# Smart_OBD.net
KiCad netlist of a schematic drawn in Altium Designer
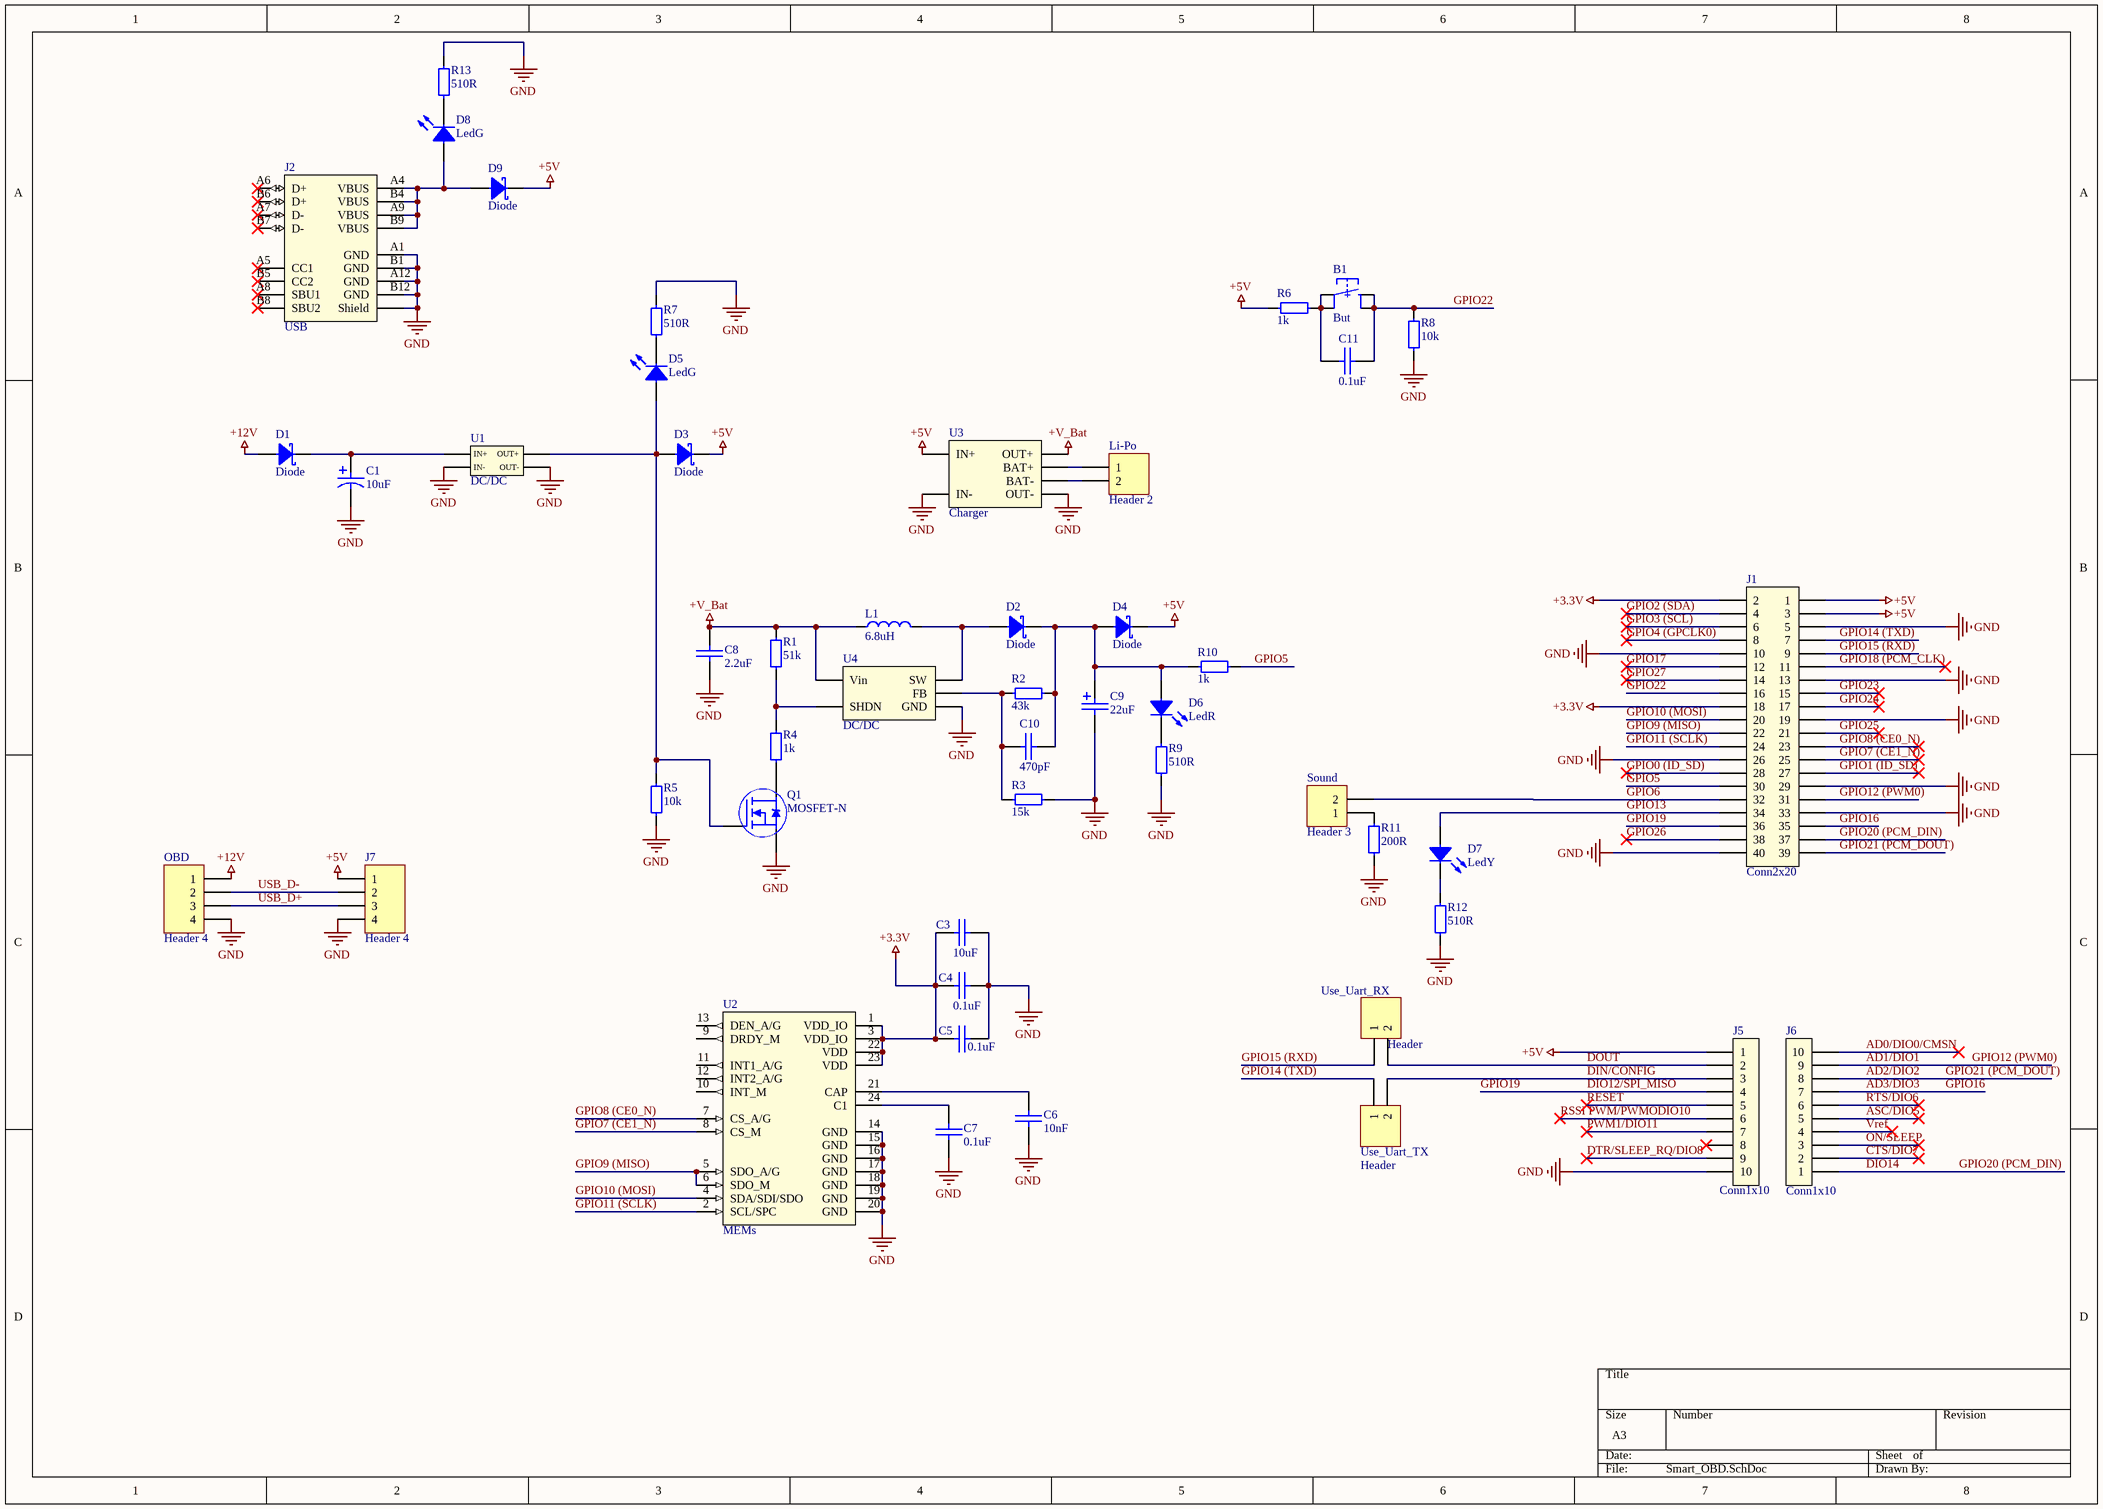
[diagram p0: Smart_OBD.SchDoc]

(export (version "E")
  (design (tool "Eeschema 10.0.6"))
  (components
    (comp (ref "B1")
      (value "But")
      (footprint "Button 6x6")
      (description "Button 4 Conn SMD")
      (fields (field (name "MANUFACTURER") "TE Connectivity") (field (name "PART NUMBER") "1571563-9"))
      (libsource (lib "Karen_Components") (part "Button 4 Conn"))
    )
    (comp (ref "C1")
      (value "10uF")
      (footprint "Bar Cap 5x5.4")
      (description "ECAP SMD,  35V")
      (fields (field (name "PART NUMBER") "ECAPSMD10uF/35V") (field (name "MANUFACTURER") "China"))
      (libsource (lib "Karen_Components") (part "Cap Pol 10uF"))
    )
    (comp (ref "C3")
      (value "10uF")
      (footprint "0603 Capicator")
      (description "10uF X5R 25V 20% 0603")
      (fields
        (field (name "MANUFACTURER") "Murata Manufacturing")
        (field (name "PART NUMBER") "GRM188R61E106M")
      )
      (libsource (lib "Karen_Components") (part "Cap 10uF (0603)"))
    )
    (comp (ref "C4")
      (value "0.1uF")
      (footprint "0603 Capicator")
      (description "0.1uF X7R 50V 10% 0603")
      (fields
        (field (name "MANUFACTURER") "Murata Manufacturing")
        (field (name "PART NUMBER") "GRM188R71H104KA93D")
      )
      (libsource (lib "Karen_Components") (part "Cap 0.1uF (0603)"))
    )
    (comp (ref "C5")
      (value "0.1uF")
      (footprint "0603 Capicator")
      (description "0.1uF X7R 50V 10% 0603")
      (fields
        (field (name "MANUFACTURER") "Murata Manufacturing")
        (field (name "PART NUMBER") "GRM188R71H104KA93D")
      )
      (libsource (lib "Karen_Components") (part "Cap 0.1uF (0603)"))
    )
    (comp (ref "C6")
      (value "10nF")
      (footprint "0603 Capicator")
      (description "X7R 10nF 100V 10% 0603")
      (fields
        (field (name "MANUFACTURER") "Murata Manufacturing")
        (field (name "PART NUMBER") "GRM188R72A103KA01D")
      )
      (libsource (lib "Karen_Components") (part "Cap 10nF (0603)"))
    )
    (comp (ref "C7")
      (value "0.1uF")
      (footprint "0603 Capicator")
      (description "0.1uF X7R 50V 10% 0603")
      (fields
        (field (name "MANUFACTURER") "Murata Manufacturing")
        (field (name "PART NUMBER") "GRM188R71H104KA93D")
      )
      (libsource (lib "Karen_Components") (part "Cap 0.1uF (0603)"))
    )
    (comp (ref "C8")
      (value "2.2uF")
      (footprint "0603 Capicator")
      (description "2.2uF X5R 10V 10% 0603")
      (fields
        (field (name "MANUFACTURER") "Murata Manufacturing")
        (field (name "PART NUMBER") "GRM188R61A225KE34D")
      )
      (libsource (lib "Karen_Components") (part "Cap 2.2uF (0603)"))
    )
    (comp (ref "C9")
      (value "22uF")
      (footprint "TANTAL_C_CASE")
      (description "TECAP, 22uF, 16V, case C, 10%")
      (fields (field (name "PART NUMBER") "TECAP22/16VC10") (field (name "MANUFACTURER") "China"))
      (libsource (lib "Karen_Components") (part "Cap Tantal 22uF (SMDC)"))
    )
    (comp (ref "C10")
      (value "470pF")
      (footprint "0603 Capicator")
      (description "470pF NP0 50V 5% 0603")
      (fields (field (name "MANUFACTURER") "Taiwan") (field (name "PART NUMBER") "MLCC470pFNPO50V5%0603"))
      (libsource (lib "Karen_Components") (part "Cap 470pF (0603)"))
    )
    (comp (ref "C11")
      (value "0.1uF")
      (footprint "0603 Capicator")
      (description "0.1uF X7R 50V 10% 0603")
      (fields
        (field (name "MANUFACTURER") "Murata Manufacturing")
        (field (name "PART NUMBER") "GRM188R71H104KA93D")
      )
      (libsource (lib "Karen_Components") (part "Cap 0.1uF (0603)"))
    )
    (comp (ref "D1")
      (value "Diode")
      (footprint "SMA")
      (description "Diode Schottky 3A 40V")
      (fields (field (name "PART NUMBER") "B340A-E3/61T") (field (name "MANUFACTURER") "Vishay"))
      (libsource (lib "Karen_Components") (part "Diode Schottky (SMA)"))
    )
    (comp (ref "D2")
      (value "Diode")
      (footprint "SMA")
      (description "Diode Schottky 3A 40V")
      (fields (field (name "PART NUMBER") "B340A-E3/61T") (field (name "MANUFACTURER") "Vishay"))
      (libsource (lib "Karen_Components") (part "Diode Schottky (SMA)"))
    )
    (comp (ref "D3")
      (value "Diode")
      (footprint "SMA")
      (description "Diode Schottky 3A 40V")
      (fields (field (name "PART NUMBER") "B340A-E3/61T") (field (name "MANUFACTURER") "Vishay"))
      (libsource (lib "Karen_Components") (part "Diode Schottky (SMA)"))
    )
    (comp (ref "D4")
      (value "Diode")
      (footprint "SMA")
      (description "Diode Schottky 3A 40V")
      (fields (field (name "PART NUMBER") "B340A-E3/61T") (field (name "MANUFACTURER") "Vishay"))
      (libsource (lib "Karen_Components") (part "Diode Schottky (SMA)"))
    )
    (comp (ref "D5")
      (value "LedG")
      (footprint "0805 LED")
      (description "Led Green SMD 1608, 120°, 525nM")
      (fields
        (field (name "PART NUMBER") "TO-1608BC-PG")
        (field (name "MANUFACTURER") "Taiwan Oasis Technology")
      )
      (libsource (lib "Karen_Components") (part "Led Green"))
    )
    (comp (ref "D6")
      (value "LedR")
      (footprint "0805 LED")
      (description "SMD 1608, 112mcd, 120°, 630nM (Ultra Bright Red)")
      (fields
        (field (name "PART NUMBER") "TO-1608BC-MRE")
        (field (name "MANUFACTURER") "Taiwan Oasis Technology")
      )
      (libsource (lib "Karen_Components") (part "Led Red"))
    )
    (comp (ref "D7")
      (value "LedY")
      (footprint "0805 LED")
      (description "SMD 1608, 247mcd, 120°, 592nM (High Bright Yellow)")
      (fields
        (field (name "PART NUMBER") "TO-1608BC-MYF")
        (field (name "MANUFACTURER") "Taiwan Oasis Technology")
      )
      (libsource (lib "Karen_Components") (part "Led Yellow"))
    )
    (comp (ref "D8")
      (value "LedG")
      (footprint "0805 LED")
      (description "Led Green SMD 1608, 120°, 525nM")
      (fields
        (field (name "PART NUMBER") "TO-1608BC-PG")
        (field (name "MANUFACTURER") "Taiwan Oasis Technology")
      )
      (libsource (lib "Karen_Components") (part "Led Green"))
    )
    (comp (ref "D9")
      (value "Diode")
      (footprint "SMA")
      (description "Diode Schottky 3A 40V")
      (fields (field (name "PART NUMBER") "B340A-E3/61T") (field (name "MANUFACTURER") "Vishay"))
      (libsource (lib "Karen_Components") (part "Diode Schottky (SMA)"))
    )
    (comp (ref "J1")
      (value "Conn2x20")
      (footprint "PBD 2x20")
      (description "Female for PLD")
      (fields
        (field (name "PART NUMBER") "DS1023-2*20S21")
        (field (name "MANUFACTURER") "Ningbo connfly electronic")
      )
      (libsource (lib "Karen_Components") (part "Conn2x20 (PBD)"))
    )
    (comp (ref "J2")
      (value "USB")
      (footprint "USB Type-C")
      (fields
        (field (name "MANUFACTURER") "Global Connector Technology")
        (field (name "PART NUMBER") "USB4085-GF-A")
      )
      (libsource (lib "Karen_Components") (part "Connector USB 2.0 Type-C"))
    )
    (comp (ref "J5")
      (value "Conn1x10")
      (footprint "PBS2 10")
      (description "Female")
      (fields
        (field (name "PART NUMBER") "DS1026-01-1*10S8BV")
        (field (name "MANUFACTURER") "Ningbo connfly electronic")
      )
      (libsource (lib "") (part "Conn1x10 (PBS2)_1"))
    )
    (comp (ref "J6")
      (value "Conn1x10")
      (footprint "PBS2 10")
      (description "Female")
      (fields
        (field (name "PART NUMBER") "DS1026-01-1*10S8BV")
        (field (name "MANUFACTURER") "Ningbo connfly electronic")
      )
      (libsource (lib "Karen_Components") (part "Conn1x10 (PBS2)"))
    )
    (comp (ref "J7")
      (value "Header 4")
      (footprint "HDR1X4")
      (description "Header, 4-Pin")
      (fields (field (name "PUBLISHER") "Altium Limited"))
      (libsource (lib "") (part "Header 4_1"))
    )
    (comp (ref "L1")
      (value "6.8uH")
      (footprint "Inductor 5.4x5.1")
      (description "6.8uH, 5.4x5.1x2, 4.2A")
      (fields (field (name "PART NUMBER") "SPM5020T-3R3M-LR") (field (name "MANUFACTURER") "TDK"))
      (libsource (lib "Karen_Components") (part "Inductor 6.8uH (4.2A)"))
    )
    (comp (ref "Li-Po")
      (value "Header 2")
      (footprint "HDR1X2")
      (description "Header, 2-Pin")
      (fields (field (name "PUBLISHER") "Altium Limited"))
      (libsource (lib "") (part "Header 2_1"))
    )
    (comp (ref "OBD")
      (value "Header 4")
      (footprint "HDR1X4")
      (description "Header, 4-Pin")
      (fields (field (name "PUBLISHER") "Altium Limited"))
      (libsource (lib "Miscellaneous Connectors") (part "Header 4"))
    )
    (comp (ref "Q1")
      (value "MOSFET-N")
      (footprint "SOT-23")
      (fields (field (name "PART NUMBER") "FDV303N") (field (name "MANUFACTURER") "Fairchild Semiconductor"))
      (libsource (lib "Karen_Components") (part "MOSFET-N [FDV]"))
    )
    (comp (ref "R1")
      (value "51k")
      (footprint "0603 Resistor")
      (description "0.1W 0603 51k, 1%")
      (fields (field (name "PART NUMBER") "RC0603FR-0751KL") (field (name "MANUFACTURER") "Taiwan"))
      (libsource (lib "Karen_Components") (part "Res 51k (0603)"))
    )
    (comp (ref "R2")
      (value "43k")
      (footprint "0603 Resistor")
      (description "0.1W 0603 43k, 1%")
      (fields (field (name "PART NUMBER") "RC0603FR-0743KL") (field (name "MANUFACTURER") "Taiwan"))
      (libsource (lib "Karen_Components") (part "Res 43k (0603)"))
    )
    (comp (ref "R3")
      (value "15k")
      (footprint "0603 Resistor")
      (description "0.1W 0603 15k, 1%")
      (fields (field (name "PART NUMBER") "RC0603FR-0715KL") (field (name "MANUFACTURER") "Taiwan"))
      (libsource (lib "Karen_Components") (part "Res 15k (0603)"))
    )
    (comp (ref "R4")
      (value "1k")
      (footprint "0603 Resistor")
      (description "0.1W 0603 1k, 1%")
      (fields (field (name "PART NUMBER") "RC0603FR-071KL") (field (name "MANUFACTURER") "Taiwan"))
      (libsource (lib "Karen_Components") (part "Res 1k (0603)"))
    )
    (comp (ref "R5")
      (value "10k")
      (footprint "0603 Resistor")
      (description "0.1W 0603 10k, 1%")
      (fields (field (name "PART NUMBER") "RC0603FR-0710KL") (field (name "MANUFACTURER") "Taiwan"))
      (libsource (lib "Karen_Components") (part "Res 10k (0603)"))
    )
    (comp (ref "R6")
      (value "1k")
      (footprint "0603 Resistor")
      (description "0.1W 0603 1k, 1%")
      (fields (field (name "PART NUMBER") "RC0603FR-071KL") (field (name "MANUFACTURER") "Taiwan"))
      (libsource (lib "Karen_Components") (part "Res 1k (0603)"))
    )
    (comp (ref "R7")
      (value "510R")
      (footprint "0603 Resistor")
      (description "0.1W 0603 510R, 1%")
      (fields (field (name "PART NUMBER") "RC0603FR-07510RL") (field (name "MANUFACTURER") "Taiwan"))
      (libsource (lib "Karen_Components") (part "Res 510R (0603)"))
    )
    (comp (ref "R8")
      (value "10k")
      (footprint "0603 Resistor")
      (description "0.1W 0603 10k, 1%")
      (fields (field (name "PART NUMBER") "RC0603FR-0710KL") (field (name "MANUFACTURER") "Taiwan"))
      (libsource (lib "Karen_Components") (part "Res 10k (0603)"))
    )
    (comp (ref "R9")
      (value "510R")
      (footprint "0603 Resistor")
      (description "0.1W 0603 510R, 1%")
      (fields (field (name "PART NUMBER") "RC0603FR-07510RL") (field (name "MANUFACTURER") "Taiwan"))
      (libsource (lib "Karen_Components") (part "Res 510R (0603)"))
    )
    (comp (ref "R10")
      (value "1k")
      (footprint "0603 Resistor")
      (description "0.1W 0603 1k, 1%")
      (fields (field (name "PART NUMBER") "RC0603FR-071KL") (field (name "MANUFACTURER") "Taiwan"))
      (libsource (lib "Karen_Components") (part "Res 1k (0603)"))
    )
    (comp (ref "R11")
      (value "200R")
      (footprint "0603 Resistor")
      (description "0.1W 0603 200R, 1%")
      (fields (field (name "PART NUMBER") "RC0603FR-07200RL") (field (name "MANUFACTURER") "Taiwan"))
      (libsource (lib "Karen_Components") (part "Res 200R (0603)"))
    )
    (comp (ref "R12")
      (value "510R")
      (footprint "0603 Resistor")
      (description "0.1W 0603 510R, 1%")
      (fields (field (name "PART NUMBER") "RC0603FR-07510RL") (field (name "MANUFACTURER") "Taiwan"))
      (libsource (lib "Karen_Components") (part "Res 510R (0603)"))
    )
    (comp (ref "R13")
      (value "510R")
      (footprint "0603 Resistor")
      (description "0.1W 0603 510R, 1%")
      (fields (field (name "PART NUMBER") "RC0603FR-07510RL") (field (name "MANUFACTURER") "Taiwan"))
      (libsource (lib "Karen_Components") (part "Res 510R (0603)"))
    )
    (comp (ref "Sound")
      (value "Header 3")
      (footprint "HDR1X2")
      (description "Header, 2-Pin")
      (fields (field (name "PUBLISHER") "Altium Limited"))
      (libsource (lib "") (part "Header 2_2"))
    )
    (comp (ref "U1")
      (value "DC/DC")
      (footprint "DC-DC")
      (description "DC/DC 5V with MP2307 Chip")
      (libsource (lib "Karen_Components") (part "DC/DC"))
    )
    (comp (ref "U2")
      (value "MEMs")
      (footprint "LGA 3.5x3x1 mm 24-lead")
      (fields (field (name "MANUFACTURER") "STMicroelectronics") (field (name "PART NUMBER") "LSM9DS1TR"))
      (libsource (lib "Karen_Components") (part "MEMs 9 Axis"))
    )
    (comp (ref "U3")
      (value "Charger")
      (footprint "PW829")
      (description "Charger for Li-Ion")
      (fields (field (name "PART NUMBER") "PW829") (field (name "MANUFACTURER") "Master Kit"))
      (libsource (lib "Karen_Components") (part "Charger [PW829]"))
    )
    (comp (ref "U4")
      (value "DC/DC")
      (footprint "SOT-23-5")
      (fields (field (name "MANUFACTURER") "Texas Instruments") (field (name "PART NUMBER") "LM2731YMF/NOPB"))
      (libsource (lib "Karen_Components") (part "DC/DC Controller [LM2731]"))
    )
    (comp (ref "Use_Uart_RX")
      (value "Header")
      (footprint "HDR1X2")
      (description "Header, 2-Pin")
      (fields (field (name "PUBLISHER") "Altium Limited"))
      (libsource (lib "Miscellaneous Connectors") (part "Header 2"))
    )
    (comp (ref "Use_Uart_TX")
      (value "Header")
      (footprint "HDR1X2")
      (description "Header, 2-Pin")
      (fields (field (name "PUBLISHER") "Altium Limited"))
      (libsource (lib "") (part "Header 2_2"))
    )
  )
  (nets
    (net (code "1") (name "+3.3V") (class "Default")
      (node (ref "C3") (pin "1") (pinfunction "1_1") (pintype "passive"))
      (node (ref "C4") (pin "1") (pinfunction "1_1") (pintype "passive"))
      (node (ref "C5") (pin "1") (pinfunction "1_1") (pintype "passive"))
      (node (ref "J1") (pin "18") (pinfunction "18_18") (pintype "passive"))
      (node (ref "J1") (pin "2") (pinfunction "2_2") (pintype "passive"))
      (node (ref "U2") (pin "1") (pinfunction "VDD_IO_1") (pintype "power_in"))
      (node (ref "U2") (pin "22") (pinfunction "VDD_22") (pintype "power_in"))
      (node (ref "U2") (pin "23") (pinfunction "VDD_23") (pintype "power_in"))
      (node (ref "U2") (pin "3") (pinfunction "VDD_IO_3") (pintype "power_in"))
    )
    (net (code "2") (name "+5V") (class "Default")
      (node (ref "D3") (pin "2") (pinfunction "2_2") (pintype "passive"))
      (node (ref "D4") (pin "2") (pinfunction "2_2") (pintype "passive"))
      (node (ref "D9") (pin "2") (pinfunction "2_2") (pintype "passive"))
      (node (ref "J1") (pin "1") (pinfunction "1_1") (pintype "passive"))
      (node (ref "J1") (pin "3") (pinfunction "3_3") (pintype "passive"))
      (node (ref "J5") (pin "1") (pinfunction "1_1") (pintype "passive"))
      (node (ref "J7") (pin "1") (pinfunction "1_1") (pintype "passive"))
      (node (ref "R6") (pin "1") (pinfunction "1_1") (pintype "passive"))
      (node (ref "U3") (pin "IN+") (pinfunction "IN+_IN+") (pintype "power_in"))
    )
    (net (code "3") (name "+12V") (class "Default")
      (node (ref "D1") (pin "1") (pinfunction "1_1") (pintype "passive"))
      (node (ref "OBD") (pin "1") (pinfunction "1_1") (pintype "passive"))
    )
    (net (code "4") (name "+V_Bat") (class "Default")
      (node (ref "C8") (pin "2") (pinfunction "2_2") (pintype "passive"))
      (node (ref "L1") (pin "1") (pinfunction "1_1") (pintype "passive"))
      (node (ref "R1") (pin "2") (pinfunction "2_2") (pintype "passive"))
      (node (ref "U3") (pin "OUT+") (pinfunction "OUT+_OUT+") (pintype "power_in"))
      (node (ref "U4") (pin "5") (pinfunction "Vin_5") (pintype "power_in"))
    )
    (net (code "5") (name "/AD0{slash}DIO0{slash}CMSN") (class "Default")
      (node (ref "J6") (pin "10") (pinfunction "10_10") (pintype "passive+no_connect"))
    )
    (net (code "6") (name "/AD1{slash}DIO1") (class "Default")
      (node (ref "J1") (pin "31") (pinfunction "31_31") (pintype "passive"))
      (node (ref "J6") (pin "9") (pinfunction "9_9") (pintype "passive"))
    )
    (net (code "7") (name "/AD2{slash}DIO2") (class "Default")
      (node (ref "J1") (pin "39") (pinfunction "39_39") (pintype "passive"))
      (node (ref "J6") (pin "8") (pinfunction "8_8") (pintype "passive"))
    )
    (net (code "8") (name "/AD3{slash}DIO3") (class "Default")
      (node (ref "J1") (pin "35") (pinfunction "35_35") (pintype "passive"))
      (node (ref "J6") (pin "7") (pinfunction "7_7") (pintype "passive"))
    )
    (net (code "9") (name "/ASC{slash}DIO5") (class "Default")
      (node (ref "J6") (pin "5") (pinfunction "5_5") (pintype "passive+no_connect"))
    )
    (net (code "10") (name "/CTS{slash}DIO7") (class "Default")
      (node (ref "J6") (pin "2") (pinfunction "2_2") (pintype "passive+no_connect"))
    )
    (net (code "11") (name "/DIN{slash}CONFIG") (class "Default")
      (node (ref "J5") (pin "3") (pinfunction "3_3") (pintype "passive"))
      (node (ref "Use_Uart_TX") (pin "2") (pinfunction "2_2") (pintype "passive"))
    )
    (net (code "12") (name "/DIO12{slash}SPI_MISO") (class "Default")
      (node (ref "J1") (pin "36") (pinfunction "36_36") (pintype "passive"))
      (node (ref "J5") (pin "4") (pinfunction "4_4") (pintype "passive"))
    )
    (net (code "13") (name "/DIO14") (class "Default")
      (node (ref "J1") (pin "37") (pinfunction "37_37") (pintype "passive"))
      (node (ref "J6") (pin "1") (pinfunction "1_1") (pintype "passive"))
    )
    (net (code "14") (name "/DOUT") (class "Default")
      (node (ref "J5") (pin "2") (pinfunction "2_2") (pintype "passive"))
      (node (ref "Use_Uart_RX") (pin "2") (pinfunction "2_2") (pintype "passive"))
    )
    (net (code "15") (name "/DTR{slash}SLEEP_RQ{slash}DIO8") (class "Default")
      (node (ref "J5") (pin "9") (pinfunction "9_9") (pintype "passive+no_connect"))
    )
    (net (code "16") (name "/GPIO0 (ID_SD)") (class "Default")
      (node (ref "J1") (pin "28") (pinfunction "28_28") (pintype "passive+no_connect"))
    )
    (net (code "17") (name "/GPIO1 (ID_SD)") (class "Default")
      (node (ref "J1") (pin "27") (pinfunction "27_27") (pintype "passive+no_connect"))
    )
    (net (code "18") (name "/GPIO2 (SDA)") (class "Default")
      (node (ref "J1") (pin "4") (pinfunction "4_4") (pintype "passive+no_connect"))
    )
    (net (code "19") (name "/GPIO3 (SCL)") (class "Default")
      (node (ref "J1") (pin "6") (pinfunction "6_6") (pintype "passive+no_connect"))
    )
    (net (code "20") (name "/GPIO4 (GPCLK0)") (class "Default")
      (node (ref "J1") (pin "8") (pinfunction "8_8") (pintype "passive+no_connect"))
    )
    (net (code "21") (name "/GPIO5") (class "Default")
      (node (ref "J1") (pin "30") (pinfunction "30_30") (pintype "passive"))
      (node (ref "R10") (pin "1") (pinfunction "1_1") (pintype "passive"))
    )
    (net (code "22") (name "/GPIO6") (class "Default")
      (node (ref "J1") (pin "32") (pinfunction "32_32") (pintype "passive"))
      (node (ref "Sound") (pin "2") (pinfunction "2_2") (pintype "passive"))
    )
    (net (code "23") (name "/GPIO7 (CE1_N)") (class "Default")
      (node (ref "J1") (pin "25") (pinfunction "25_25") (pintype "passive"))
      (node (ref "U2") (pin "8") (pinfunction "CS_M_8") (pintype "input"))
    )
    (net (code "24") (name "/GPIO8 (CE0_N)") (class "Default")
      (node (ref "J1") (pin "23") (pinfunction "23_23") (pintype "passive"))
      (node (ref "U2") (pin "7") (pinfunction "CS_A/G_7") (pintype "input"))
    )
    (net (code "25") (name "/GPIO9 (MISO)") (class "Default")
      (node (ref "J1") (pin "22") (pinfunction "22_22") (pintype "passive"))
      (node (ref "U2") (pin "5") (pinfunction "SDO_A/G_5") (pintype "input"))
      (node (ref "U2") (pin "6") (pinfunction "SDO_M_6") (pintype "input"))
    )
    (net (code "26") (name "/GPIO10 (MOSI)") (class "Default")
      (node (ref "J1") (pin "20") (pinfunction "20_20") (pintype "passive"))
      (node (ref "U2") (pin "4") (pinfunction "SDA/SDI/SDO_4") (pintype "input"))
    )
    (net (code "27") (name "/GPIO11 (SCLK)") (class "Default")
      (node (ref "J1") (pin "24") (pinfunction "24_24") (pintype "passive"))
      (node (ref "U2") (pin "2") (pinfunction "SCL/SPC_2") (pintype "input"))
    )
    (net (code "28") (name "/GPIO13") (class "Default")
      (node (ref "D7") (pin "1") (pinfunction "1_1") (pintype "passive"))
      (node (ref "J1") (pin "34") (pinfunction "34_34") (pintype "passive"))
    )
    (net (code "29") (name "/GPIO14 (TXD)") (class "Default")
      (node (ref "J1") (pin "7") (pinfunction "7_7") (pintype "passive"))
      (node (ref "Use_Uart_TX") (pin "1") (pinfunction "1_1") (pintype "passive"))
    )
    (net (code "30") (name "/GPIO15 (RXD)") (class "Default")
      (node (ref "J1") (pin "9") (pinfunction "9_9") (pintype "passive"))
      (node (ref "Use_Uart_RX") (pin "1") (pinfunction "1_1") (pintype "passive"))
    )
    (net (code "31") (name "/GPIO17") (class "Default")
      (node (ref "J1") (pin "12") (pinfunction "12_12") (pintype "passive+no_connect"))
    )
    (net (code "32") (name "/GPIO18 (PCM_CLK)") (class "Default")
      (node (ref "J1") (pin "11") (pinfunction "11_11") (pintype "passive+no_connect"))
    )
    (net (code "33") (name "/GPIO22") (class "Default")
      (node (ref "B1") (pin "3") (pinfunction "3_3") (pintype "passive"))
      (node (ref "B1") (pin "4") (pinfunction "4_4") (pintype "passive"))
      (node (ref "C11") (pin "2") (pinfunction "2_2") (pintype "passive"))
      (node (ref "J1") (pin "16") (pinfunction "16_16") (pintype "passive"))
      (node (ref "R8") (pin "2") (pinfunction "2_2") (pintype "passive"))
    )
    (net (code "34") (name "/GPIO23") (class "Default")
      (node (ref "J1") (pin "15") (pinfunction "15_15") (pintype "passive+no_connect"))
    )
    (net (code "35") (name "/GPIO24") (class "Default")
      (node (ref "J1") (pin "17") (pinfunction "17_17") (pintype "passive+no_connect"))
    )
    (net (code "36") (name "/GPIO25") (class "Default")
      (node (ref "J1") (pin "21") (pinfunction "21_21") (pintype "passive+no_connect"))
    )
    (net (code "37") (name "/GPIO26") (class "Default")
      (node (ref "J1") (pin "38") (pinfunction "38_38") (pintype "passive+no_connect"))
    )
    (net (code "38") (name "/GPIO27") (class "Default")
      (node (ref "J1") (pin "14") (pinfunction "14_14") (pintype "passive+no_connect"))
    )
    (net (code "39") (name "/ON{slash}SLEEP") (class "Default")
      (node (ref "J6") (pin "3") (pinfunction "3_3") (pintype "passive+no_connect"))
    )
    (net (code "40") (name "/PWM1{slash}DIO11") (class "Default")
      (node (ref "J5") (pin "7") (pinfunction "7_7") (pintype "passive+no_connect"))
    )
    (net (code "41") (name "/RESET") (class "Default")
      (node (ref "J5") (pin "5") (pinfunction "5_5") (pintype "passive+no_connect"))
    )
    (net (code "42") (name "/RSSI PWM{slash}PWMODIO10") (class "Default")
      (node (ref "J5") (pin "6") (pinfunction "6_6") (pintype "passive+no_connect"))
    )
    (net (code "43") (name "/RTS{slash}DIO6") (class "Default")
      (node (ref "J6") (pin "6") (pinfunction "6_6") (pintype "passive+no_connect"))
    )
    (net (code "44") (name "/USB_D+") (class "Default")
      (node (ref "J7") (pin "3") (pinfunction "3_3") (pintype "passive"))
      (node (ref "OBD") (pin "3") (pinfunction "3_3") (pintype "passive"))
    )
    (net (code "45") (name "/USB_D-") (class "Default")
      (node (ref "J7") (pin "2") (pinfunction "2_2") (pintype "passive"))
      (node (ref "OBD") (pin "2") (pinfunction "2_2") (pintype "passive"))
    )
    (net (code "46") (name "/Vref") (class "Default")
      (node (ref "J6") (pin "4") (pinfunction "4_4") (pintype "passive+no_connect"))
    )
    (net (code "47") (name "GND") (class "Default")
      (node (ref "C1") (pin "1") (pinfunction "1_1") (pintype "passive"))
      (node (ref "C3") (pin "2") (pinfunction "2_2") (pintype "passive"))
      (node (ref "C4") (pin "2") (pinfunction "2_2") (pintype "passive"))
      (node (ref "C5") (pin "2") (pinfunction "2_2") (pintype "passive"))
      (node (ref "C6") (pin "2") (pinfunction "2_2") (pintype "passive"))
      (node (ref "C7") (pin "2") (pinfunction "2_2") (pintype "passive"))
      (node (ref "C8") (pin "1") (pinfunction "1_1") (pintype "passive"))
      (node (ref "C9") (pin "1") (pinfunction "1_1") (pintype "passive"))
      (node (ref "J1") (pin "10") (pinfunction "10_10") (pintype "passive"))
      (node (ref "J1") (pin "13") (pinfunction "13_13") (pintype "passive"))
      (node (ref "J1") (pin "19") (pinfunction "19_19") (pintype "passive"))
      (node (ref "J1") (pin "26") (pinfunction "26_26") (pintype "passive"))
      (node (ref "J1") (pin "29") (pinfunction "29_29") (pintype "passive"))
      (node (ref "J1") (pin "33") (pinfunction "33_33") (pintype "passive"))
      (node (ref "J1") (pin "40") (pinfunction "40_40") (pintype "passive"))
      (node (ref "J1") (pin "5") (pinfunction "5_5") (pintype "passive"))
      (node (ref "J2") (pin "A") (pinfunction "Shield_A") (pintype "power_in"))
      (node (ref "J2") (pin "A1") (pinfunction "GND_A1") (pintype "power_in"))
      (node (ref "J2") (pin "A12") (pinfunction "GND_A12") (pintype "power_in"))
      (node (ref "J2") (pin "B1") (pinfunction "GND_B1") (pintype "power_in"))
      (node (ref "J2") (pin "B12") (pinfunction "GND_B12") (pintype "power_in"))
      (node (ref "J5") (pin "10") (pinfunction "10_10") (pintype "passive"))
      (node (ref "J7") (pin "4") (pinfunction "4_4") (pintype "passive"))
      (node (ref "OBD") (pin "4") (pinfunction "4_4") (pintype "passive"))
      (node (ref "Q1") (pin "2") (pinfunction "Source_2") (pintype "passive"))
      (node (ref "R11") (pin "1") (pinfunction "1_1") (pintype "passive"))
      (node (ref "R12") (pin "2") (pinfunction "2_2") (pintype "passive"))
      (node (ref "R13") (pin "2") (pinfunction "2_2") (pintype "passive"))
      (node (ref "R3") (pin "2") (pinfunction "2_2") (pintype "passive"))
      (node (ref "R5") (pin "1") (pinfunction "1_1") (pintype "passive"))
      (node (ref "R7") (pin "2") (pinfunction "2_2") (pintype "passive"))
      (node (ref "R8") (pin "1") (pinfunction "1_1") (pintype "passive"))
      (node (ref "R9") (pin "2") (pinfunction "2_2") (pintype "passive"))
      (node (ref "U1") (pin "1") (pinfunction "IN-_1") (pintype "passive"))
      (node (ref "U1") (pin "3") (pinfunction "OUT-_3") (pintype "passive"))
      (node (ref "U2") (pin "14") (pinfunction "GND_14") (pintype "power_in"))
      (node (ref "U2") (pin "15") (pinfunction "GND_15") (pintype "power_in"))
      (node (ref "U2") (pin "16") (pinfunction "GND_16") (pintype "power_in"))
      (node (ref "U2") (pin "17") (pinfunction "GND_17") (pintype "power_in"))
      (node (ref "U2") (pin "18") (pinfunction "GND_18") (pintype "power_in"))
      (node (ref "U2") (pin "19") (pinfunction "GND_19") (pintype "power_in"))
      (node (ref "U2") (pin "20") (pinfunction "GND_20") (pintype "power_in"))
      (node (ref "U3") (pin "IN-") (pinfunction "IN-_IN-") (pintype "power_in"))
      (node (ref "U3") (pin "OUT-") (pinfunction "OUT-_OUT-") (pintype "power_in"))
      (node (ref "U4") (pin "2") (pinfunction "GND_2") (pintype "power_in"))
    )
    (net (code "48") (name "Net-(B1-Pad1)") (class "Default")
      (node (ref "B1") (pin "1") (pinfunction "1_1") (pintype "passive"))
      (node (ref "B1") (pin "2") (pinfunction "2_2") (pintype "passive"))
      (node (ref "C11") (pin "1") (pinfunction "1_1") (pintype "passive"))
      (node (ref "R6") (pin "2") (pinfunction "2_2") (pintype "passive"))
    )
    (net (code "49") (name "Net-(C10-Pad2)") (class "Default")
      (node (ref "C10") (pin "2") (pinfunction "2_2") (pintype "passive"))
      (node (ref "C9") (pin "2") (pinfunction "2_2") (pintype "passive"))
      (node (ref "D2") (pin "2") (pinfunction "2_2") (pintype "passive"))
      (node (ref "D4") (pin "1") (pinfunction "1_1") (pintype "passive"))
      (node (ref "D6") (pin "1") (pinfunction "1_1") (pintype "passive"))
      (node (ref "R10") (pin "2") (pinfunction "2_2") (pintype "passive"))
      (node (ref "R2") (pin "2") (pinfunction "2_2") (pintype "passive"))
    )
    (net (code "50") (name "Net-(D5-Pad2)") (class "Default")
      (node (ref "D5") (pin "2") (pinfunction "2_2") (pintype "passive"))
      (node (ref "R7") (pin "1") (pinfunction "1_1") (pintype "passive"))
    )
    (net (code "51") (name "Net-(D6-Pad2)") (class "Default")
      (node (ref "D6") (pin "2") (pinfunction "2_2") (pintype "passive"))
      (node (ref "R9") (pin "1") (pinfunction "1_1") (pintype "passive"))
    )
    (net (code "52") (name "Net-(D7-Pad2)") (class "Default")
      (node (ref "D7") (pin "2") (pinfunction "2_2") (pintype "passive"))
      (node (ref "R12") (pin "1") (pinfunction "1_1") (pintype "passive"))
    )
    (net (code "53") (name "Net-(D8-Pad1)") (class "Default")
      (node (ref "D8") (pin "1") (pinfunction "1_1") (pintype "passive"))
      (node (ref "D9") (pin "1") (pinfunction "1_1") (pintype "passive"))
      (node (ref "J2") (pin "A4") (pinfunction "VBUS_A4") (pintype "power_in"))
      (node (ref "J2") (pin "A9") (pinfunction "VBUS_A9") (pintype "power_in"))
      (node (ref "J2") (pin "B4") (pinfunction "VBUS_B4") (pintype "power_in"))
      (node (ref "J2") (pin "B9") (pinfunction "VBUS_B9") (pintype "power_in"))
    )
    (net (code "54") (name "Net-(D8-Pad2)") (class "Default")
      (node (ref "D8") (pin "2") (pinfunction "2_2") (pintype "passive"))
      (node (ref "R13") (pin "1") (pinfunction "1_1") (pintype "passive"))
    )
    (net (code "55") (name "Net-(Q1-Drain)") (class "Default")
      (node (ref "Q1") (pin "3") (pinfunction "Drain_3") (pintype "passive"))
      (node (ref "R4") (pin "1") (pinfunction "1_1") (pintype "passive"))
    )
    (net (code "56") (name "Net-(Q1-Gate)") (class "Default")
      (node (ref "D3") (pin "1") (pinfunction "1_1") (pintype "passive"))
      (node (ref "D5") (pin "1") (pinfunction "1_1") (pintype "passive"))
      (node (ref "Q1") (pin "1") (pinfunction "Gate_1") (pintype "passive"))
      (node (ref "R5") (pin "2") (pinfunction "2_2") (pintype "passive"))
      (node (ref "U1") (pin "4") (pinfunction "OUT+_4") (pintype "passive"))
    )
    (net (code "57") (name "Net-(R11-Pad2)") (class "Default")
      (node (ref "R11") (pin "2") (pinfunction "2_2") (pintype "passive"))
      (node (ref "Sound") (pin "1") (pinfunction "1_1") (pintype "passive"))
    )
    (net (code "58") (name "Net-(U1-IN+)") (class "Default")
      (node (ref "C1") (pin "2") (pinfunction "2_2") (pintype "passive"))
      (node (ref "D1") (pin "2") (pinfunction "2_2") (pintype "passive"))
      (node (ref "U1") (pin "2") (pinfunction "IN+_2") (pintype "passive"))
    )
    (net (code "59") (name "Net-(U2-C1)") (class "Default")
      (node (ref "C7") (pin "1") (pinfunction "1_1") (pintype "passive"))
      (node (ref "U2") (pin "24") (pinfunction "C1_24") (pintype "open_collector"))
    )
    (net (code "60") (name "Net-(U2-CAP)") (class "Default")
      (node (ref "C6") (pin "1") (pinfunction "1_1") (pintype "passive"))
      (node (ref "U2") (pin "21") (pinfunction "CAP_21") (pintype "open_collector"))
    )
    (net (code "61") (name "Net-(U3-BAT+)") (class "Default")
      (node (ref "Li-Po") (pin "1") (pinfunction "1_1") (pintype "passive"))
      (node (ref "U3") (pin "B+") (pinfunction "BAT+_B+") (pintype "power_in"))
    )
    (net (code "62") (name "Net-(U3-BAT-)") (class "Default")
      (node (ref "Li-Po") (pin "2") (pinfunction "2_2") (pintype "passive"))
      (node (ref "U3") (pin "B-") (pinfunction "BAT-_B-") (pintype "power_in"))
    )
    (net (code "63") (name "Net-(U4-FB)") (class "Default")
      (node (ref "C10") (pin "1") (pinfunction "1_1") (pintype "passive"))
      (node (ref "R2") (pin "1") (pinfunction "1_1") (pintype "passive"))
      (node (ref "R3") (pin "1") (pinfunction "1_1") (pintype "passive"))
      (node (ref "U4") (pin "3") (pinfunction "FB_3") (pintype "passive"))
    )
    (net (code "64") (name "Net-(U4-SHDN)") (class "Default")
      (node (ref "R1") (pin "1") (pinfunction "1_1") (pintype "passive"))
      (node (ref "R4") (pin "2") (pinfunction "2_2") (pintype "passive"))
      (node (ref "U4") (pin "4") (pinfunction "SHDN_4") (pintype "power_in"))
    )
    (net (code "65") (name "Net-(U4-SW)") (class "Default")
      (node (ref "D2") (pin "1") (pinfunction "1_1") (pintype "passive"))
      (node (ref "L1") (pin "2") (pinfunction "2_2") (pintype "passive"))
      (node (ref "U4") (pin "1") (pinfunction "SW_1") (pintype "passive"))
    )
    (net (code "66") (name "unconnected-(J2-CC1-PadA5)") (class "Default")
      (node (ref "J2") (pin "A5") (pinfunction "CC1_A5") (pintype "passive+no_connect"))
    )
    (net (code "67") (name "unconnected-(J2-CC2-PadB5)") (class "Default")
      (node (ref "J2") (pin "B5") (pinfunction "CC2_B5") (pintype "passive+no_connect"))
    )
    (net (code "68") (name "unconnected-(J2-D+-PadA6)") (class "Default")
      (node (ref "J2") (pin "A6") (pinfunction "D+_A6") (pintype "bidirectional+no_connect"))
    )
    (net (code "69") (name "unconnected-(J2-D+-PadB6)") (class "Default")
      (node (ref "J2") (pin "B6") (pinfunction "D+_B6") (pintype "bidirectional+no_connect"))
    )
    (net (code "70") (name "unconnected-(J2-D--PadA7)") (class "Default")
      (node (ref "J2") (pin "A7") (pinfunction "D-_A7") (pintype "bidirectional+no_connect"))
    )
    (net (code "71") (name "unconnected-(J2-D--PadB7)") (class "Default")
      (node (ref "J2") (pin "B7") (pinfunction "D-_B7") (pintype "bidirectional+no_connect"))
    )
    (net (code "72") (name "unconnected-(J2-SBU1-PadA8)") (class "Default")
      (node (ref "J2") (pin "A8") (pinfunction "SBU1_A8") (pintype "passive+no_connect"))
    )
    (net (code "73") (name "unconnected-(J2-SBU2-PadB8)") (class "Default")
      (node (ref "J2") (pin "B8") (pinfunction "SBU2_B8") (pintype "passive+no_connect"))
    )
    (net (code "74") (name "unconnected-(J5-Pad8)") (class "Default")
      (node (ref "J5") (pin "8") (pinfunction "8_8") (pintype "passive+no_connect"))
    )
    (net (code "75") (name "unconnected-(U2-DEN_A{slash}G-Pad13)") (class "Default")
      (node (ref "U2") (pin "13") (pinfunction "DEN_A/G_13") (pintype "output"))
    )
    (net (code "76") (name "unconnected-(U2-DRDY_M-Pad9)") (class "Default")
      (node (ref "U2") (pin "9") (pinfunction "DRDY_M_9") (pintype "output"))
    )
    (net (code "77") (name "unconnected-(U2-INT1_A{slash}G-Pad11)") (class "Default")
      (node (ref "U2") (pin "11") (pinfunction "INT1_A/G_11") (pintype "output"))
    )
    (net (code "78") (name "unconnected-(U2-INT2_A{slash}G-Pad12)") (class "Default")
      (node (ref "U2") (pin "12") (pinfunction "INT2_A/G_12") (pintype "output"))
    )
    (net (code "79") (name "unconnected-(U2-INT_M-Pad10)") (class "Default")
      (node (ref "U2") (pin "10") (pinfunction "INT_M_10") (pintype "output"))
    )
  )
)
